# encoder.net
KiCad netlist of a schematic drawn in Altium Designer
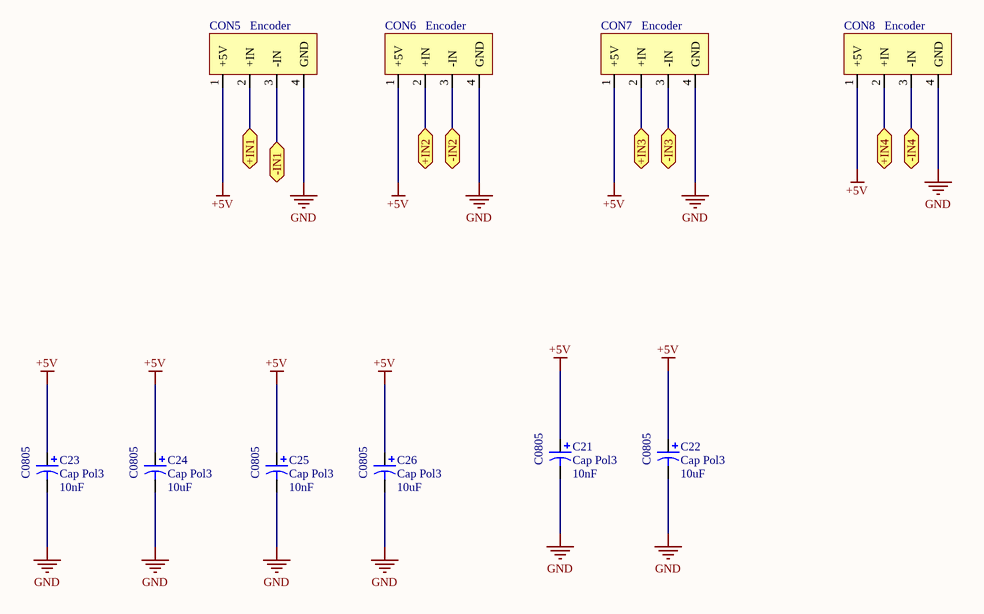
[diagram p0: encoder.SchDoc]

(export (version "E")
  (design (tool "Eeschema 10.0.6"))
  (components
    (comp (ref "C21")
      (value "Cap Pol3")
      (footprint "C0805")
      (description "Polarized Capacitor (Surface Mount)")
      (fields
        (field (name "PACKAGEREFERENCE") "C0805")
        (field (name "ALTIUM_VALUE") "10nF")
        (field (name "PUBLISHER") "Altium Limited")
      )
      (libsource (lib "Miscellaneous Devices") (part "Cap Pol3"))
    )
    (comp (ref "C22")
      (value "Cap Pol3")
      (footprint "C0805")
      (description "Polarized Capacitor (Surface Mount)")
      (fields
        (field (name "PACKAGEREFERENCE") "C0805")
        (field (name "ALTIUM_VALUE") "10uF")
        (field (name "PUBLISHER") "Altium Limited")
      )
      (libsource (lib "Miscellaneous Devices") (part "Cap Pol3"))
    )
    (comp (ref "C23")
      (value "Cap Pol3")
      (footprint "C0805")
      (description "Polarized Capacitor (Surface Mount)")
      (fields
        (field (name "PACKAGEREFERENCE") "C0805")
        (field (name "ALTIUM_VALUE") "10nF")
        (field (name "PUBLISHER") "Altium Limited")
      )
      (libsource (lib "Miscellaneous Devices") (part "Cap Pol3"))
    )
    (comp (ref "C24")
      (value "Cap Pol3")
      (footprint "C0805")
      (description "Polarized Capacitor (Surface Mount)")
      (fields
        (field (name "PACKAGEREFERENCE") "C0805")
        (field (name "ALTIUM_VALUE") "10uF")
        (field (name "PUBLISHER") "Altium Limited")
      )
      (libsource (lib "Miscellaneous Devices") (part "Cap Pol3"))
    )
    (comp (ref "C25")
      (value "Cap Pol3")
      (footprint "C0805")
      (description "Polarized Capacitor (Surface Mount)")
      (fields
        (field (name "PACKAGEREFERENCE") "C0805")
        (field (name "ALTIUM_VALUE") "10nF")
        (field (name "PUBLISHER") "Altium Limited")
      )
      (libsource (lib "Miscellaneous Devices") (part "Cap Pol3"))
    )
    (comp (ref "C26")
      (value "Cap Pol3")
      (footprint "C0805")
      (description "Polarized Capacitor (Surface Mount)")
      (fields
        (field (name "PACKAGEREFERENCE") "C0805")
        (field (name "ALTIUM_VALUE") "10uF")
        (field (name "PUBLISHER") "Altium Limited")
      )
      (libsource (lib "Miscellaneous Devices") (part "Cap Pol3"))
    )
    (comp (ref "CON5") (value "Encoder") (footprint "ENCODER") (libsource (lib "ATMEGA126") (part "Encoder")))
    (comp (ref "CON6") (value "Encoder") (footprint "ENCODER") (libsource (lib "ATMEGA126") (part "Encoder")))
    (comp (ref "CON7") (value "Encoder") (footprint "ENCODER") (libsource (lib "ATMEGA126") (part "Encoder")))
    (comp (ref "CON8") (value "Encoder") (footprint "ENCODER") (libsource (lib "ATMEGA126") (part "Encoder")))
  )
  (nets
    (net (code "1") (name "+5V") (class "Default")
      (node (ref "C21") (pin "1") (pinfunction "1_1") (pintype "passive"))
      (node (ref "C22") (pin "1") (pinfunction "1_1") (pintype "passive"))
      (node (ref "C23") (pin "1") (pinfunction "1_1") (pintype "passive"))
      (node (ref "C24") (pin "1") (pinfunction "1_1") (pintype "passive"))
      (node (ref "C25") (pin "1") (pinfunction "1_1") (pintype "passive"))
      (node (ref "C26") (pin "1") (pinfunction "1_1") (pintype "passive"))
      (node (ref "CON5") (pin "1") (pinfunction "+5V_1") (pintype "power_in"))
      (node (ref "CON6") (pin "1") (pinfunction "+5V_1") (pintype "power_in"))
      (node (ref "CON7") (pin "1") (pinfunction "+5V_1") (pintype "power_in"))
      (node (ref "CON8") (pin "1") (pinfunction "+5V_1") (pintype "power_in"))
    )
    (net (code "2") (name "/+IN1") (class "Default")
      (node (ref "CON5") (pin "2") (pinfunction "+IN_2") (pintype "passive"))
    )
    (net (code "3") (name "/+IN2") (class "Default")
      (node (ref "CON6") (pin "2") (pinfunction "+IN_2") (pintype "passive"))
    )
    (net (code "4") (name "/+IN3") (class "Default")
      (node (ref "CON7") (pin "2") (pinfunction "+IN_2") (pintype "passive"))
    )
    (net (code "5") (name "/+IN4") (class "Default")
      (node (ref "CON8") (pin "2") (pinfunction "+IN_2") (pintype "passive"))
    )
    (net (code "6") (name "/-IN1") (class "Default")
      (node (ref "CON5") (pin "3") (pinfunction "-IN_3") (pintype "passive"))
    )
    (net (code "7") (name "/-IN2") (class "Default")
      (node (ref "CON6") (pin "3") (pinfunction "-IN_3") (pintype "passive"))
    )
    (net (code "8") (name "/-IN3") (class "Default")
      (node (ref "CON7") (pin "3") (pinfunction "-IN_3") (pintype "passive"))
    )
    (net (code "9") (name "/-IN4") (class "Default")
      (node (ref "CON8") (pin "3") (pinfunction "-IN_3") (pintype "passive"))
    )
    (net (code "10") (name "GND") (class "Default")
      (node (ref "C21") (pin "2") (pinfunction "2_2") (pintype "passive"))
      (node (ref "C22") (pin "2") (pinfunction "2_2") (pintype "passive"))
      (node (ref "C23") (pin "2") (pinfunction "2_2") (pintype "passive"))
      (node (ref "C24") (pin "2") (pinfunction "2_2") (pintype "passive"))
      (node (ref "C25") (pin "2") (pinfunction "2_2") (pintype "passive"))
      (node (ref "C26") (pin "2") (pinfunction "2_2") (pintype "passive"))
      (node (ref "CON5") (pin "4") (pinfunction "GND_4") (pintype "power_in"))
      (node (ref "CON6") (pin "4") (pinfunction "GND_4") (pintype "power_in"))
      (node (ref "CON7") (pin "4") (pinfunction "GND_4") (pintype "power_in"))
      (node (ref "CON8") (pin "4") (pinfunction "GND_4") (pintype "power_in"))
    )
  )
)
